# Pump.net
KiCad netlist of a schematic drawn in Altium Designer
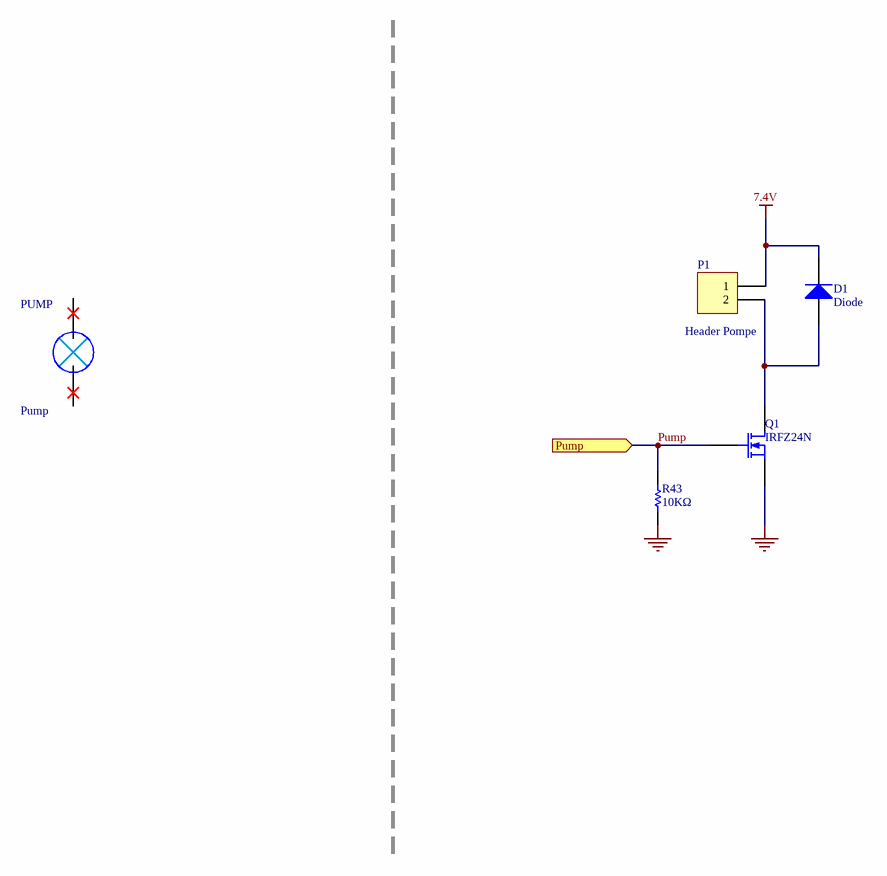
[diagram p0: Pump.SchDoc]

(export (version "E")
  (design (tool "Eeschema 10.0.6"))
  (components
    (comp (ref "D1")
      (value "Diode")
      (footprint "DO-219AB")
      (fields (field (name "PUBLISHER") "Altium Limited"))
      (libsource (lib "Miscellaneous Devices") (part "Diode"))
    )
    (comp (ref "P1")
      (value "Header Pompe")
      (footprint "BORNIER")
      (description "Header, 2-Pin")
      (fields
        (field (name "MANUFACTURER") "BUCHANAN - TE CONNECTIVITY")
        (field (name "PUBLISHER") "Altium Limited")
      )
      (libsource (lib "Miscellaneous Connectors") (part "Header 2"))
    )
    (comp (ref "PUMP")
      (value "Pump")
      (fields (field (name "MANUFACTURER") "/"))
      (libsource (lib "Electroplant") (part "Pump"))
    )
    (comp (ref "Q1")
      (value "IRFZ24N")
      (footprint "TO-220AB")
      (description "N-Channel MOSFET")
      (fields (field (name "MANUFACTURER") "INFINEON") (field (name "PUBLISHER") "Altium Limited"))
      (libsource (lib "Miscellaneous Devices") (part "MOSFET-N"))
    )
    (comp (ref "R43")
      (value "10KΩ")
      (footprint "R0603")
      (description "Resistor")
      (fields (field (name "MANUFACTURER") "MULTICOMP") (field (name "PUBLISHER") "Altium Limited"))
      (libsource (lib "Miscellaneous Devices") (part "Res1"))
    )
  )
  (nets
    (net (code "1") (name "/Pump") (class "Default")
      (node (ref "Q1") (pin "2") (pinfunction "G_2") (pintype "passive"))
      (node (ref "R43") (pin "1") (pinfunction "1_1") (pintype "passive"))
    )
    (net (code "2") (name "7.4V") (class "Default")
      (node (ref "D1") (pin "2") (pinfunction "K_2") (pintype "passive"))
      (node (ref "P1") (pin "1") (pinfunction "1_1") (pintype "passive"))
    )
    (net (code "3") (name "GND") (class "Default")
      (node (ref "Q1") (pin "3") (pinfunction "S_3") (pintype "passive"))
      (node (ref "R43") (pin "2") (pinfunction "2_2") (pintype "passive"))
    )
    (net (code "4") (name "Net-(D1-A)") (class "Default")
      (node (ref "D1") (pin "1") (pinfunction "A_1") (pintype "passive"))
      (node (ref "P1") (pin "2") (pinfunction "2_2") (pintype "passive"))
      (node (ref "Q1") (pin "1") (pinfunction "D_1") (pintype "passive"))
    )
    (net (code "5") (name "unconnected-(PUMP-Pad1)") (class "Default")
      (node (ref "PUMP") (pin "1") (pinfunction "1_1") (pintype "passive"))
    )
    (net (code "6") (name "unconnected-(PUMP-Pad2)") (class "Default")
      (node (ref "PUMP") (pin "2") (pinfunction "2_2") (pintype "passive"))
    )
  )
)
